# Microcontroller.net
KiCad netlist of a schematic drawn in Altium Designer
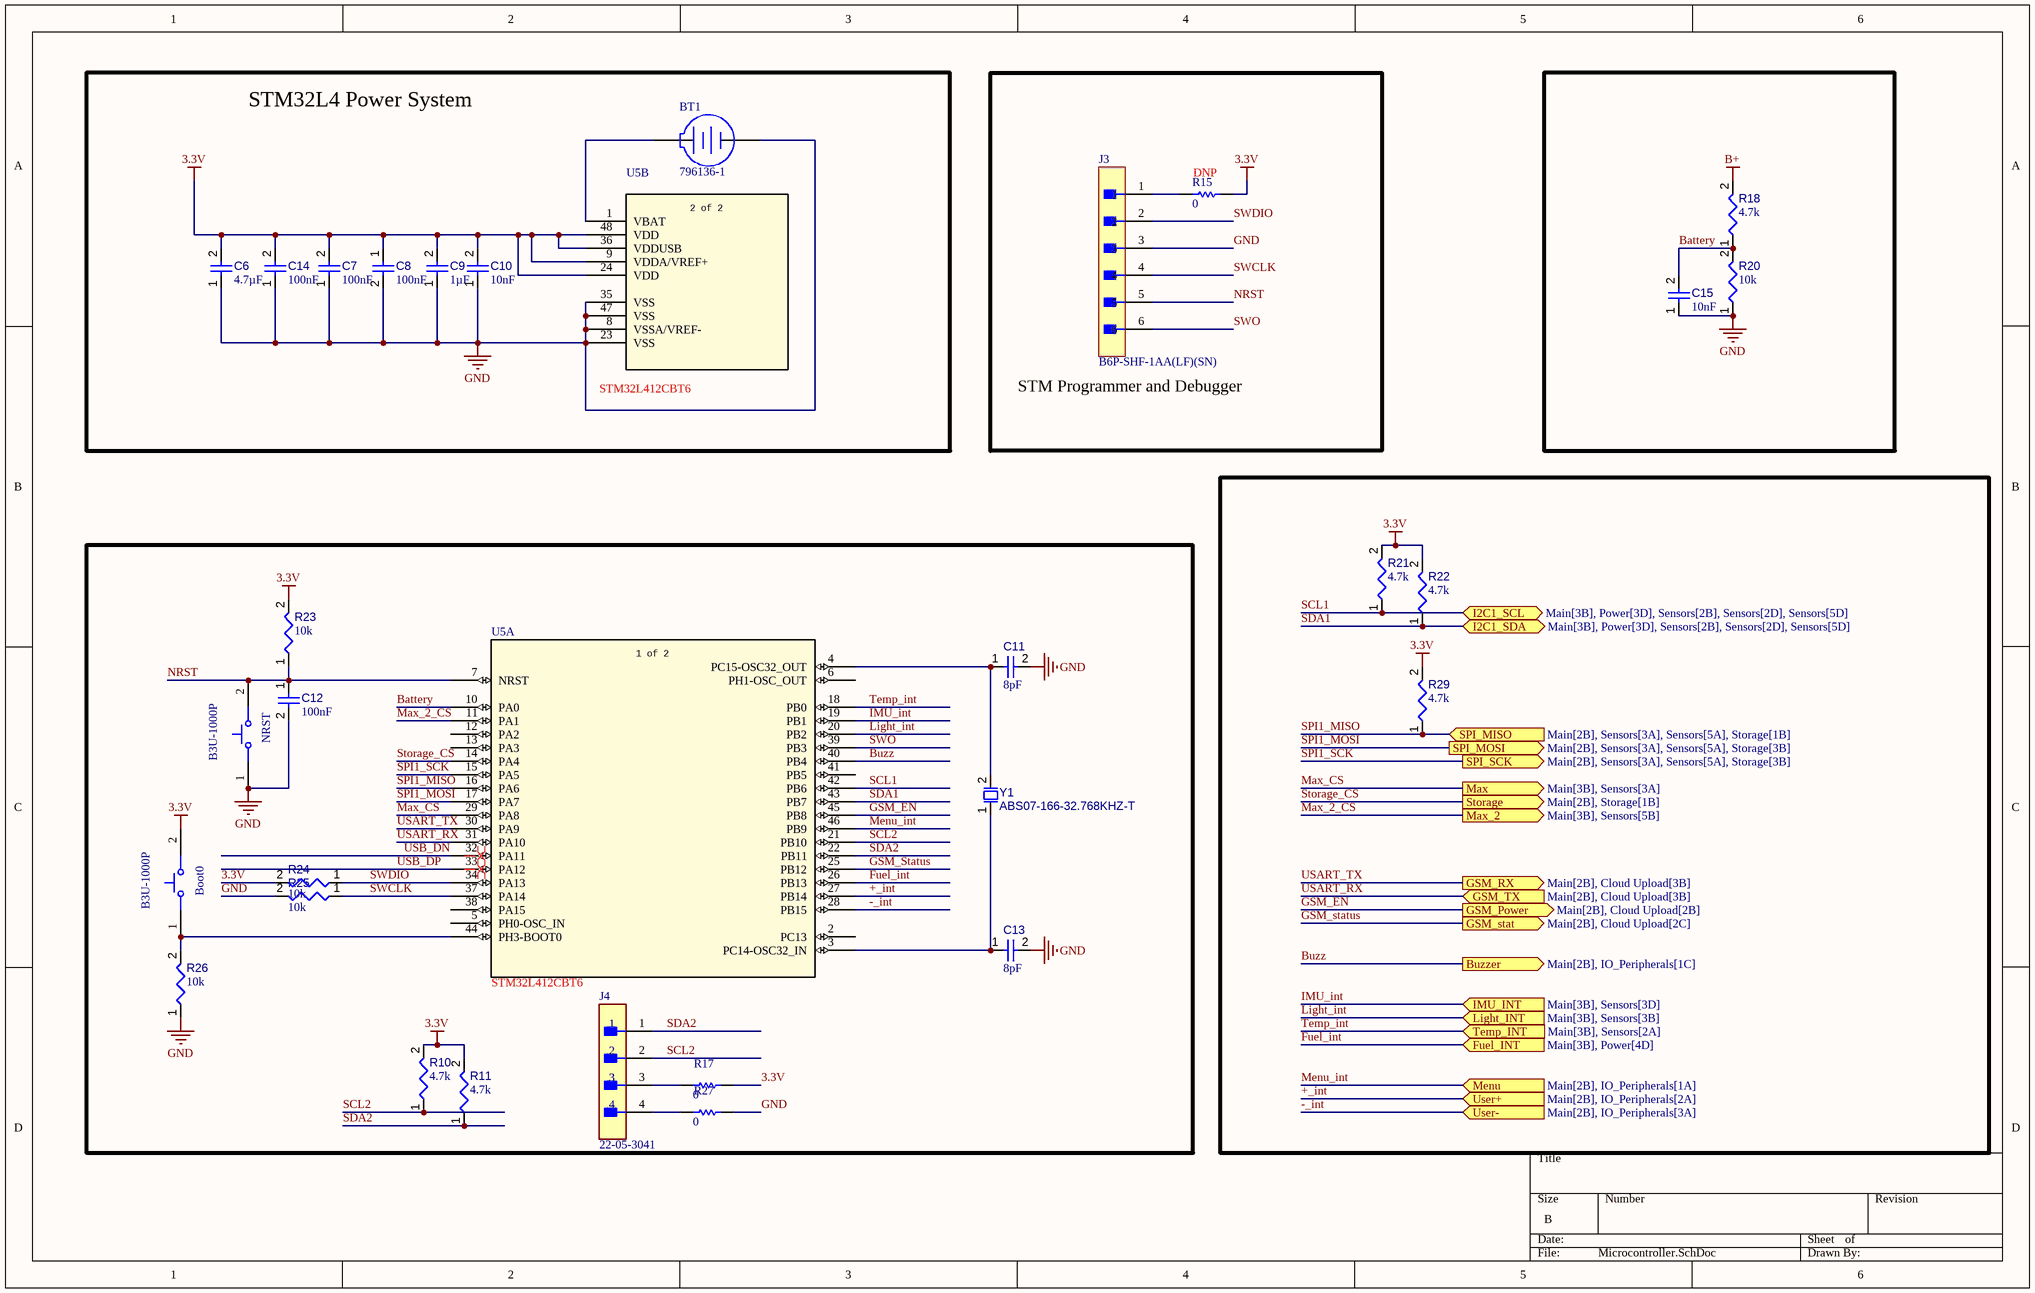
[diagram p0: Microcontroller.SchDoc]

(export (version "E")
  (design (tool "Eeschema 10.0.6"))
  (components
    (comp (ref "Boot0")
      (value "B3U-1000P")
      (footprint "OMRON-B3U-1000_V")
      (description "Tactile Switch, SPST-NO, 0.05 A, 12 V, -25 to 70 degC, 2-Pin SMD, RoHS, Tape and Reel")
      (fields (field (name "MANUFACTURER") "Omron Electronic Components"))
      (libsource (lib "Buddhi Rashmika") (part "SW-SPST-NO-2"))
    )
    (comp (ref "BT1")
      (value "796136-1")
      (footprint "TECO-796136-1_V")
      (description "Battery Connector, 1 Cell, CR2032, 2-Pin SMD, RoHS, Tape and Reel")
      (fields (field (name "MANUFACTURER") "TE Connectivity"))
      (libsource (lib "Buddhi Rashmika") (part "BATTERY-HOLDER-COIN-2"))
    )
    (comp (ref "C6")
      (value "4.7µF")
      (footprint "CAPC0603(1608)100_L")
      (description "Chip Capacitor, 4.7µF +/-20%, 10V, 0603, Thickness 1 mm")
      (fields (field (name "TOLERANCE") "10%") (field (name "Comment") "Capacitor 4.7µF +/-20% 10V 0603"))
      (libsource (lib "Buddhi Rashmika") (part "CAP-NP-2"))
    )
    (comp (ref "C7")
      (value "100nF")
      (footprint "FP-GCJ188-0_2-IPC_C")
      (description "16V 100nF X7R ±10% 0603 Multilayer Ceramic Capacitors MLCC - SMD/SMT ROHS")
      (fields (field (name "TOLERANCE") "10%") (field (name "Comment") "GCJ188R71C104KA01D"))
      (libsource (lib "Buddhi Rashmika") (part "CAP-NP-2"))
    )
    (comp (ref "C8")
      (value "100nF")
      (footprint "FP-GCJ188-0_2-IPC_C")
      (description "16V 100nF X7R ±10% 0603 Multilayer Ceramic Capacitors MLCC - SMD/SMT ROHS")
      (fields (field (name "TOLERANCE") "10%") (field (name "Comment") "GCJ188R71C104KA01D"))
      (libsource (lib "Buddhi Rashmika") (part "CAP-NP-2"))
    )
    (comp (ref "C9")
      (value "1µF")
      (footprint "CAPC1608X90X35ML15T15")
      (description "Chip Capacitor, 1 uF, +/- 10%, 16 V, 0603 (1608 Metric)")
      (fields (field (name "TOLERANCE") "10%") (field (name "Comment") "Capacitor 1uF +/- 10% 16V 0603"))
      (libsource (lib "Buddhi Rashmika") (part "CAP-NP-2"))
    )
    (comp (ref "C10")
      (value "10nF")
      (footprint "CAPC1608X95X40ML15T15")
      (fields (field (name "TOLERANCE") "10%") (field (name "Comment") "VJ0603Y103KXQCW1BC"))
      (libsource (lib "Buddhi Rashmika") (part "CAP-NP-2"))
    )
    (comp (ref "C11")
      (value "8pF")
      (footprint "FP-GCM188-0_1-IPC_B")
      (description "100V 8pF C0G 0603 Multilayer Ceramic Capacitors MLCC - SMD/SMT ROHS")
      (fields (field (name "Comment") "GCM1885C2A8R0DA16D"))
      (libsource (lib "Buddhi Rashmika") (part "CAP-NP-2"))
    )
    (comp (ref "C12")
      (value "100nF")
      (footprint "FP-GCJ188-0_2-IPC_C")
      (description "16V 100nF X7R ±10% 0603 Multilayer Ceramic Capacitors MLCC - SMD/SMT ROHS")
      (fields (field (name "TOLERANCE") "10%") (field (name "Comment") "GCJ188R71C104KA01D"))
      (libsource (lib "Buddhi Rashmika") (part "CAP-NP-2"))
    )
    (comp (ref "C13")
      (value "8pF")
      (footprint "FP-GCM188-0_1-IPC_B")
      (description "100V 8pF C0G 0603 Multilayer Ceramic Capacitors MLCC - SMD/SMT ROHS")
      (fields (field (name "Comment") "GCM1885C2A8R0DA16D"))
      (libsource (lib "Buddhi Rashmika") (part "CAP-NP-2"))
    )
    (comp (ref "C14")
      (value "100nF")
      (footprint "FP-GCJ188-0_2-IPC_C")
      (description "16V 100nF X7R ±10% 0603 Multilayer Ceramic Capacitors MLCC - SMD/SMT ROHS")
      (fields (field (name "TOLERANCE") "10%") (field (name "Comment") "GCJ188R71C104KA01D"))
      (libsource (lib "Buddhi Rashmika") (part "CAP-NP-2"))
    )
    (comp (ref "C15")
      (value "10nF")
      (footprint "CAPC1608X95X40ML15T15")
      (fields (field (name "TOLERANCE") "10%") (field (name "Comment") "VJ0603Y103KXQCW1BC"))
      (libsource (lib "Buddhi Rashmika") (part "CAP-NP-2"))
    )
    (comp (ref "J3")
      (value "B6P-SHF-1AA(LF)(SN)")
      (footprint "FP-B6P-SHF-1AA_LF_SN-MFG")
      (description "Connector Header, NH Series, 6 Position, Top Entry, 2.5mm, 250V, 30-22 AWG, Natural")
      (libsource (lib "Buddhi Rashmika") (part "B6P-SHF-1AA_LF_SN"))
    )
    (comp (ref "J4")
      (value "22-05-3041")
      (footprint "FP-22-05-3041-MFG")
      (description "KK 254 Solid Header, Right-Angle, with Friction Lock, 4 Circuits, Tin (Sn) Plating")
      (libsource (lib "Buddhi Rashmika") (part "299a8cea1bdcbc3624fe62c390fa72c"))
    )
    (comp (ref "NRST")
      (value "B3U-1000P")
      (footprint "OMRON-B3U-1000_V")
      (description "Tactile Switch, SPST-NO, 0.05 A, 12 V, -25 to 70 degC, 2-Pin SMD, RoHS, Tape and Reel")
      (fields (field (name "MANUFACTURER") "Omron Electronic Components"))
      (libsource (lib "Buddhi Rashmika") (part "SW-SPST-NO-2"))
    )
    (comp (ref "R10")
      (value "4.7k")
      (footprint "RESC1608X55X25ML10T15")
      (description "Chip Resistor, 4.7 KOhm, +/- 1%, 0.1 W, -55 to 155 degC, 0603 (1608 Metric)")
      (fields (field (name "TOLERANCE") "1%") (field (name "POWER") "100mW"))
      (libsource (lib "Buddhi Rashmika") (part "RES-2"))
    )
    (comp (ref "R11")
      (value "4.7k")
      (footprint "RESC1608X55X25ML10T15")
      (description "Chip Resistor, 4.7 KOhm, +/- 1%, 0.1 W, -55 to 155 degC, 0603 (1608 Metric)")
      (fields (field (name "TOLERANCE") "1%") (field (name "POWER") "100mW"))
      (libsource (lib "Buddhi Rashmika") (part "RES-2"))
    )
    (comp (ref "R15")
      (value "0")
      (footprint "RESC3116X70X50ML13T20")
      (description "Chip Resistor, 0 Ohm, 0.25 W, -55 to 155 degC, 1206 (3216 Metric)")
      (fields (field (name "TOLERANCE") "0.05%") (field (name "POWER") "250mW"))
      (libsource (lib "") (part "RES-2_1"))
    )
    (comp (ref "R17")
      (value "0")
      (footprint "RESC1608X55X25ML10T15")
      (description "Chip Resistor, 0 Ohm, 0.1 W, -55 to 155 degC, 0603 (1608 Metric)")
      (fields (field (name "POWER") "100mW") (field (name "TOLERANCE") "5%"))
      (libsource (lib "") (part "RES-2_1"))
    )
    (comp (ref "R18")
      (value "4.7k")
      (footprint "RESC1608X55X25ML10T15")
      (description "Chip Resistor, 4.7 KOhm, +/- 1%, 0.1 W, -55 to 155 degC, 0603 (1608 Metric)")
      (fields (field (name "TOLERANCE") "1%") (field (name "POWER") "100mW"))
      (libsource (lib "Buddhi Rashmika") (part "RES-2"))
    )
    (comp (ref "R20")
      (value "10k")
      (footprint "RESC2013X50X35ML15T15")
      (description "Chip Resistor, 10 KOhm, +/- 1%, 125 mW, -55 to 155 degC, 0805 (2012 Metric)")
      (fields (field (name "TOLERANCE") "1%") (field (name "POWER") "125mW"))
      (libsource (lib "Buddhi Rashmika") (part "RES-2"))
    )
    (comp (ref "R21")
      (value "4.7k")
      (footprint "RESC1608X55X25ML10T15")
      (description "Chip Resistor, 4.7 KOhm, +/- 1%, 0.1 W, -55 to 155 degC, 0603 (1608 Metric)")
      (fields (field (name "TOLERANCE") "1%") (field (name "POWER") "100mW"))
      (libsource (lib "Buddhi Rashmika") (part "RES-2"))
    )
    (comp (ref "R22")
      (value "4.7k")
      (footprint "RESC1608X55X25ML10T15")
      (description "Chip Resistor, 4.7 KOhm, +/- 1%, 0.1 W, -55 to 155 degC, 0603 (1608 Metric)")
      (fields (field (name "TOLERANCE") "1%") (field (name "POWER") "100mW"))
      (libsource (lib "Buddhi Rashmika") (part "RES-2"))
    )
    (comp (ref "R23")
      (value "10k")
      (footprint "RESC2013X50X35ML15T15")
      (description "Chip Resistor, 10 KOhm, +/- 1%, 125 mW, -55 to 155 degC, 0805 (2012 Metric)")
      (fields (field (name "TOLERANCE") "1%") (field (name "POWER") "125mW"))
      (libsource (lib "Buddhi Rashmika") (part "RES-2"))
    )
    (comp (ref "R24")
      (value "10k")
      (footprint "RESC2013X50X35ML15T15")
      (description "Chip Resistor, 10 KOhm, +/- 1%, 125 mW, -55 to 155 degC, 0805 (2012 Metric)")
      (fields (field (name "TOLERANCE") "1%") (field (name "POWER") "125mW"))
      (libsource (lib "Buddhi Rashmika") (part "RES-2"))
    )
    (comp (ref "R25")
      (value "10k")
      (footprint "RESC2013X50X35ML15T15")
      (description "Chip Resistor, 10 KOhm, +/- 1%, 125 mW, -55 to 155 degC, 0805 (2012 Metric)")
      (fields (field (name "TOLERANCE") "1%") (field (name "POWER") "125mW"))
      (libsource (lib "Buddhi Rashmika") (part "RES-2"))
    )
    (comp (ref "R26")
      (value "10k")
      (footprint "RESC2013X50X35ML15T15")
      (description "Chip Resistor, 10 KOhm, +/- 1%, 125 mW, -55 to 155 degC, 0805 (2012 Metric)")
      (fields (field (name "TOLERANCE") "1%") (field (name "POWER") "125mW"))
      (libsource (lib "Buddhi Rashmika") (part "RES-2"))
    )
    (comp (ref "R27")
      (value "0")
      (footprint "RESC1608X55X25ML10T15")
      (description "Chip Resistor, 0 Ohm, 0.1 W, -55 to 155 degC, 0603 (1608 Metric)")
      (fields (field (name "POWER") "100mW") (field (name "TOLERANCE") "5%"))
      (libsource (lib "") (part "RES-2_1"))
    )
    (comp (ref "R29")
      (value "4.7k")
      (footprint "RESC1608X55X25ML10T15")
      (description "Chip Resistor, 4.7 KOhm, +/- 1%, 0.1 W, -55 to 155 degC, 0603 (1608 Metric)")
      (fields (field (name "TOLERANCE") "1%") (field (name "POWER") "100mW"))
      (libsource (lib "Buddhi Rashmika") (part "RES-2"))
    )
    (comp (ref "U5")
      (value "STM32L412CBT6")
      (footprint "LQFP-48")
      (description "Ultra-low-power with FPU Arm Cortex-M4 MCU 80 MHz with 128 Kbytes of Flash memory, USB")
      (fields (field (name "COPYRIGHT") "Copyright (C) 2026 Ultra Librarian. All rights reserved."))
      (libsource (lib "Schlib1") (part "STM32L412CBT6"))
    )
    (comp (ref "Y1")
      (value "ABS07-166-32.768KHZ-T")
      (footprint "EPSON-FC-135_V")
      (description "Crystal 32.768kHz 10ppm 7pF -40C +85C")
      (libsource (lib "Buddhi Rashmika") (part "CMP-001-0024-1"))
    )
  )
  (nets
    (net (code "1") (name "/+_int") (class "Default")
      (node (ref "U5") (pin "27") (pinfunction "PB14_27") (pintype "bidirectional"))
    )
    (net (code "2") (name "/-_int") (class "Default")
      (node (ref "U5") (pin "28") (pinfunction "PB15_28") (pintype "bidirectional"))
    )
    (net (code "3") (name "/Battery") (class "Default")
      (node (ref "C15") (pin "2") (pinfunction "2_2") (pintype "passive"))
      (node (ref "R18") (pin "1") (pinfunction "1_1") (pintype "passive"))
      (node (ref "R20") (pin "2") (pinfunction "2_2") (pintype "passive"))
      (node (ref "U5") (pin "10") (pinfunction "PA0_10") (pintype "bidirectional"))
    )
    (net (code "4") (name "/Buzz") (class "Default")
      (node (ref "U5") (pin "40") (pinfunction "PB4_40") (pintype "bidirectional"))
    )
    (net (code "5") (name "/Fuel_int") (class "Default")
      (node (ref "U5") (pin "26") (pinfunction "PB13_26") (pintype "bidirectional"))
    )
    (net (code "6") (name "/GSM_EN") (class "Default")
      (node (ref "U5") (pin "45") (pinfunction "PB8_45") (pintype "bidirectional"))
    )
    (net (code "7") (name "/GSM_Status") (class "Default")
      (node (ref "U5") (pin "25") (pinfunction "PB12_25") (pintype "bidirectional"))
    )
    (net (code "9") (name "/IMU_int") (class "Default")
      (node (ref "U5") (pin "19") (pinfunction "PB1_19") (pintype "bidirectional"))
    )
    (net (code "10") (name "/Light_int") (class "Default")
      (node (ref "U5") (pin "20") (pinfunction "PB2_20") (pintype "bidirectional"))
    )
    (net (code "11") (name "/Max_2_CS") (class "Default")
      (node (ref "U5") (pin "11") (pinfunction "PA1_11") (pintype "bidirectional"))
    )
    (net (code "12") (name "/Max_CS") (class "Default")
      (node (ref "U5") (pin "29") (pinfunction "PA8_29") (pintype "bidirectional"))
    )
    (net (code "13") (name "/Menu_int") (class "Default")
      (node (ref "U5") (pin "46") (pinfunction "PB9_46") (pintype "bidirectional"))
    )
    (net (code "14") (name "/NRST") (class "Default")
      (node (ref "C12") (pin "1") (pinfunction "1_1") (pintype "passive"))
      (node (ref "J3") (pin "5") (pinfunction "5_5") (pintype "passive"))
      (node (ref "NRST") (pin "2") (pinfunction "2_2") (pintype "passive"))
      (node (ref "R23") (pin "1") (pinfunction "1_1") (pintype "passive"))
      (node (ref "U5") (pin "7") (pinfunction "NRST_7") (pintype "bidirectional"))
    )
    (net (code "15") (name "/SCL1") (class "Default")
      (node (ref "R21") (pin "1") (pinfunction "1_1") (pintype "passive"))
      (node (ref "U5") (pin "42") (pinfunction "PB6_42") (pintype "bidirectional"))
    )
    (net (code "16") (name "/SCL2") (class "Default")
      (node (ref "J4") (pin "2") (pinfunction "2_2") (pintype "passive"))
      (node (ref "R10") (pin "1") (pinfunction "1_1") (pintype "passive"))
      (node (ref "U5") (pin "21") (pinfunction "PB10_21") (pintype "bidirectional"))
    )
    (net (code "17") (name "/SDA1") (class "Default")
      (node (ref "R22") (pin "1") (pinfunction "1_1") (pintype "passive"))
      (node (ref "U5") (pin "43") (pinfunction "PB7_43") (pintype "bidirectional"))
    )
    (net (code "18") (name "/SDA2") (class "Default")
      (node (ref "J4") (pin "1") (pinfunction "1_1") (pintype "passive"))
      (node (ref "R11") (pin "1") (pinfunction "1_1") (pintype "passive"))
      (node (ref "U5") (pin "22") (pinfunction "PB11_22") (pintype "bidirectional"))
    )
    (net (code "19") (name "/SPI1_MISO") (class "Default")
      (node (ref "R29") (pin "1") (pinfunction "1_1") (pintype "passive"))
      (node (ref "U5") (pin "16") (pinfunction "PA6_16") (pintype "bidirectional"))
    )
    (net (code "20") (name "/SPI1_MOSI") (class "Default")
      (node (ref "U5") (pin "17") (pinfunction "PA7_17") (pintype "bidirectional"))
    )
    (net (code "21") (name "/SPI1_SCK") (class "Default")
      (node (ref "U5") (pin "15") (pinfunction "PA5_15") (pintype "bidirectional"))
    )
    (net (code "22") (name "/SWCLK") (class "Default")
      (node (ref "J3") (pin "4") (pinfunction "4_4") (pintype "passive"))
      (node (ref "R25") (pin "1") (pinfunction "1_1") (pintype "passive"))
      (node (ref "U5") (pin "37") (pinfunction "PA14_37") (pintype "bidirectional"))
    )
    (net (code "23") (name "/SWDIO") (class "Default")
      (node (ref "J3") (pin "2") (pinfunction "2_2") (pintype "passive"))
      (node (ref "R24") (pin "1") (pinfunction "1_1") (pintype "passive"))
      (node (ref "U5") (pin "34") (pinfunction "PA13_34") (pintype "bidirectional"))
    )
    (net (code "24") (name "/SWO") (class "Default")
      (node (ref "J3") (pin "6") (pinfunction "6_6") (pintype "passive"))
      (node (ref "U5") (pin "39") (pinfunction "PB3_39") (pintype "bidirectional"))
    )
    (net (code "25") (name "/Storage_CS") (class "Default")
      (node (ref "U5") (pin "14") (pinfunction "PA4_14") (pintype "bidirectional"))
    )
    (net (code "26") (name "/Temp_int") (class "Default")
      (node (ref "U5") (pin "18") (pinfunction "PB0_18") (pintype "bidirectional"))
    )
    (net (code "27") (name "/USART_RX") (class "Default")
      (node (ref "U5") (pin "31") (pinfunction "PA10_31") (pintype "bidirectional"))
    )
    (net (code "28") (name "/USART_TX") (class "Default")
      (node (ref "U5") (pin "30") (pinfunction "PA9_30") (pintype "bidirectional"))
    )
    (net (code "29") (name "/USB_DN") (class "Default")
      (node (ref "U5") (pin "32") (pinfunction "PA11_32") (pintype "bidirectional"))
    )
    (net (code "30") (name "/USB_DP") (class "Default")
      (node (ref "U5") (pin "33") (pinfunction "PA12_33") (pintype "bidirectional"))
    )
    (net (code "31") (name "3.3V") (class "Default")
      (node (ref "Boot0") (pin "2") (pinfunction "2_2") (pintype "passive"))
      (node (ref "C10") (pin "2") (pinfunction "2_2") (pintype "passive"))
      (node (ref "C14") (pin "2") (pinfunction "2_2") (pintype "passive"))
      (node (ref "C6") (pin "2") (pinfunction "2_2") (pintype "passive"))
      (node (ref "C7") (pin "2") (pinfunction "2_2") (pintype "passive"))
      (node (ref "C8") (pin "1") (pinfunction "1_1") (pintype "passive"))
      (node (ref "C9") (pin "2") (pinfunction "2_2") (pintype "passive"))
      (node (ref "R10") (pin "2") (pinfunction "2_2") (pintype "passive"))
      (node (ref "R11") (pin "2") (pinfunction "2_2") (pintype "passive"))
      (node (ref "R15") (pin "2") (pinfunction "2_2") (pintype "passive"))
      (node (ref "R17") (pin "2") (pinfunction "2_2") (pintype "passive"))
      (node (ref "R21") (pin "2") (pinfunction "2_2") (pintype "passive"))
      (node (ref "R22") (pin "2") (pinfunction "2_2") (pintype "passive"))
      (node (ref "R23") (pin "2") (pinfunction "2_2") (pintype "passive"))
      (node (ref "R24") (pin "2") (pinfunction "2_2") (pintype "passive"))
      (node (ref "R29") (pin "2") (pinfunction "2_2") (pintype "passive"))
      (node (ref "U5") (pin "24") (pinfunction "VDD_24") (pintype "power_in"))
      (node (ref "U5") (pin "36") (pinfunction "VDDUSB_36") (pintype "power_in"))
      (node (ref "U5") (pin "48") (pinfunction "VDD_48") (pintype "power_in"))
      (node (ref "U5") (pin "9") (pinfunction "VDDA/VREF+_9") (pintype "power_in"))
    )
    (net (code "32") (name "B+") (class "Default")
      (node (ref "R18") (pin "2") (pinfunction "2_2") (pintype "passive"))
    )
    (net (code "33") (name "GND") (class "Default")
      (node (ref "BT1") (pin "2") (pinfunction "-_2") (pintype "passive"))
      (node (ref "C10") (pin "1") (pinfunction "1_1") (pintype "passive"))
      (node (ref "C11") (pin "2") (pinfunction "2_2") (pintype "passive"))
      (node (ref "C12") (pin "2") (pinfunction "2_2") (pintype "passive"))
      (node (ref "C13") (pin "2") (pinfunction "2_2") (pintype "passive"))
      (node (ref "C14") (pin "1") (pinfunction "1_1") (pintype "passive"))
      (node (ref "C15") (pin "1") (pinfunction "1_1") (pintype "passive"))
      (node (ref "C6") (pin "1") (pinfunction "1_1") (pintype "passive"))
      (node (ref "C7") (pin "1") (pinfunction "1_1") (pintype "passive"))
      (node (ref "C8") (pin "2") (pinfunction "2_2") (pintype "passive"))
      (node (ref "C9") (pin "1") (pinfunction "1_1") (pintype "passive"))
      (node (ref "J3") (pin "3") (pinfunction "3_3") (pintype "passive"))
      (node (ref "NRST") (pin "1") (pinfunction "1_1") (pintype "passive"))
      (node (ref "R20") (pin "1") (pinfunction "1_1") (pintype "passive"))
      (node (ref "R25") (pin "2") (pinfunction "2_2") (pintype "passive"))
      (node (ref "R26") (pin "1") (pinfunction "1_1") (pintype "passive"))
      (node (ref "R27") (pin "2") (pinfunction "2_2") (pintype "passive"))
      (node (ref "U5") (pin "23") (pinfunction "VSS_23") (pintype "power_in"))
      (node (ref "U5") (pin "35") (pinfunction "VSS_35") (pintype "power_in"))
      (node (ref "U5") (pin "47") (pinfunction "VSS_47") (pintype "power_in"))
      (node (ref "U5") (pin "8") (pinfunction "VSSA/VREF-_8") (pintype "power_in"))
    )
    (net (code "34") (name "Net-(BT1-+)") (class "Default")
      (node (ref "BT1") (pin "1") (pinfunction "+_1") (pintype "passive"))
      (node (ref "U5") (pin "1") (pinfunction "VBAT_1") (pintype "power_in"))
    )
    (net (code "35") (name "Net-(J3-Pad1)") (class "Default")
      (node (ref "J3") (pin "1") (pinfunction "1_1") (pintype "passive"))
      (node (ref "R15") (pin "1") (pinfunction "1_1") (pintype "passive"))
    )
    (net (code "36") (name "Net-(J4-Pad3)") (class "Default")
      (node (ref "J4") (pin "3") (pinfunction "3_3") (pintype "passive"))
      (node (ref "R17") (pin "1") (pinfunction "1_1") (pintype "passive"))
    )
    (net (code "37") (name "Net-(J4-Pad4)") (class "Default")
      (node (ref "J4") (pin "4") (pinfunction "4_4") (pintype "passive"))
      (node (ref "R27") (pin "1") (pinfunction "1_1") (pintype "passive"))
    )
    (net (code "38") (name "Net-(U5A-PC14-OSC32_IN)") (class "Default")
      (node (ref "C13") (pin "1") (pinfunction "1_1") (pintype "passive"))
      (node (ref "U5") (pin "3") (pinfunction "PC14-OSC32_IN_3") (pintype "bidirectional"))
      (node (ref "Y1") (pin "1") (pinfunction "1_1") (pintype "passive"))
    )
    (net (code "39") (name "Net-(U5A-PC15-OSC32_OUT)") (class "Default")
      (node (ref "C11") (pin "1") (pinfunction "1_1") (pintype "passive"))
      (node (ref "U5") (pin "4") (pinfunction "PC15-OSC32_OUT_4") (pintype "bidirectional"))
      (node (ref "Y1") (pin "2") (pinfunction "2_2") (pintype "passive"))
    )
    (net (code "40") (name "Net-(U5A-PH3-BOOT0)") (class "Default")
      (node (ref "Boot0") (pin "1") (pinfunction "1_1") (pintype "passive"))
      (node (ref "R26") (pin "2") (pinfunction "2_2") (pintype "passive"))
      (node (ref "U5") (pin "44") (pinfunction "PH3-BOOT0_44") (pintype "bidirectional"))
    )
    (net (code "41") (name "unconnected-(U5A-PA2-Pad12)") (class "Default")
      (node (ref "U5") (pin "12") (pinfunction "PA2_12") (pintype "bidirectional"))
    )
    (net (code "42") (name "unconnected-(U5A-PA3-Pad13)") (class "Default")
      (node (ref "U5") (pin "13") (pinfunction "PA3_13") (pintype "bidirectional"))
    )
    (net (code "43") (name "unconnected-(U5A-PA15-Pad38)") (class "Default")
      (node (ref "U5") (pin "38") (pinfunction "PA15_38") (pintype "bidirectional"))
    )
    (net (code "44") (name "unconnected-(U5A-PB5-Pad41)") (class "Default")
      (node (ref "U5") (pin "41") (pinfunction "PB5_41") (pintype "bidirectional"))
    )
    (net (code "45") (name "unconnected-(U5A-PC13-Pad2)") (class "Default")
      (node (ref "U5") (pin "2") (pinfunction "PC13_2") (pintype "bidirectional"))
    )
    (net (code "46") (name "unconnected-(U5A-PH0-OSC_IN-Pad5)") (class "Default")
      (node (ref "U5") (pin "5") (pinfunction "PH0-OSC_IN_5") (pintype "bidirectional"))
    )
    (net (code "47") (name "unconnected-(U5A-PH1-OSC_OUT-Pad6)") (class "Default")
      (node (ref "U5") (pin "6") (pinfunction "PH1-OSC_OUT_6") (pintype "bidirectional"))
    )
  )
)
